# MM32F3277_Balance.net
KiCad netlist of a schematic drawn in Altium Designer
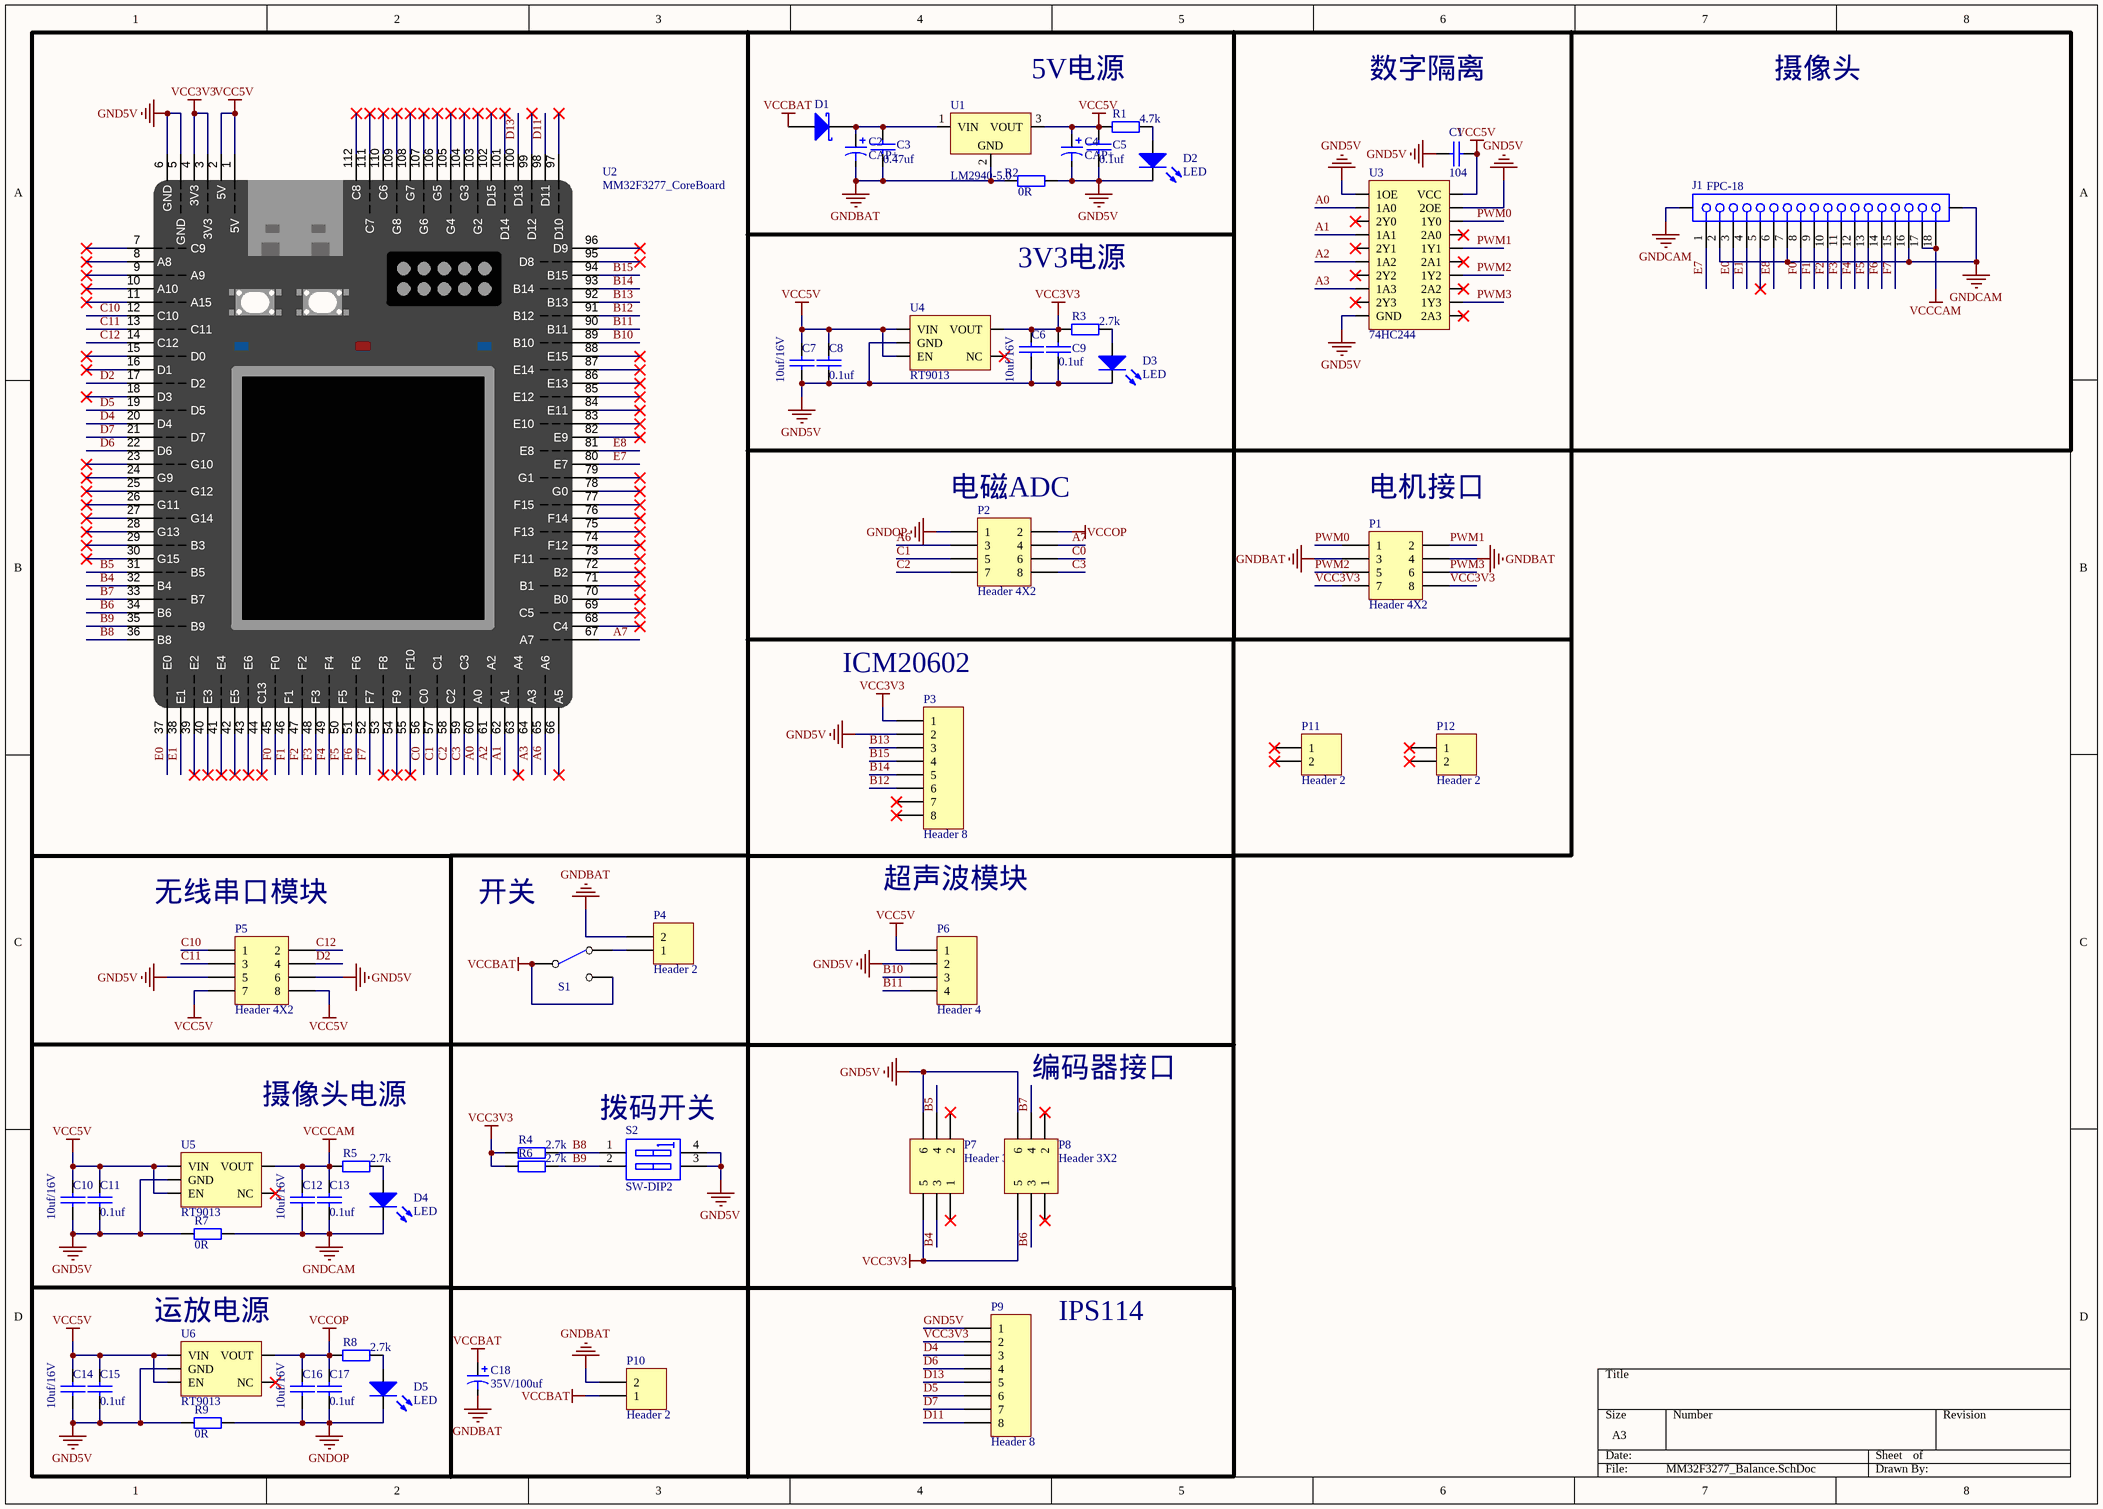
[diagram p0: MM32F3277_Balance.SchDoc]

(export (version "E")
  (design (tool "Eeschema 10.0.6"))
  (components
    (comp (ref "C1")
      (value "104")
      (footprint "0603C")
      (description "Capacitor")
      (libsource (lib "ywh") (part "CAP"))
    )
    (comp (ref "C2")
      (value "CAP+")
      (footprint "CS 2.5*6.3*11 - V")
      (description "Capacitor")
      (libsource (lib "ywh") (part "CAP+"))
    )
    (comp (ref "C3")
      (value "0.47uf")
      (footprint "0603C")
      (description "Capacitor")
      (libsource (lib "ywh") (part "CAP"))
    )
    (comp (ref "C4")
      (value "CAP+")
      (footprint "CS 2.5*6.3*7 - R")
      (description "Capacitor")
      (libsource (lib "ywh") (part "CAP+"))
    )
    (comp (ref "C5")
      (value "0.1uf")
      (footprint "0603C")
      (description "Capacitor")
      (libsource (lib "ywh") (part "CAP"))
    )
    (comp (ref "C6")
      (value "10uf/16V")
      (footprint "1206C")
      (description "Capacitor")
      (libsource (lib "ywh") (part "CAP"))
    )
    (comp (ref "C7")
      (value "10uf/16V")
      (footprint "1206C")
      (description "Capacitor")
      (libsource (lib "ywh") (part "CAP"))
    )
    (comp (ref "C8")
      (value "0.1uf")
      (footprint "0603C")
      (description "Capacitor")
      (libsource (lib "ywh") (part "CAP"))
    )
    (comp (ref "C9")
      (value "0.1uf")
      (footprint "0603C")
      (description "Capacitor")
      (libsource (lib "ywh") (part "CAP"))
    )
    (comp (ref "C10")
      (value "10uf/16V")
      (footprint "1206C")
      (description "Capacitor")
      (libsource (lib "ywh") (part "CAP"))
    )
    (comp (ref "C11")
      (value "0.1uf")
      (footprint "0603C")
      (description "Capacitor")
      (libsource (lib "ywh") (part "CAP"))
    )
    (comp (ref "C12")
      (value "10uf/16V")
      (footprint "1206C")
      (description "Capacitor")
      (libsource (lib "ywh") (part "CAP"))
    )
    (comp (ref "C13")
      (value "0.1uf")
      (footprint "0603C")
      (description "Capacitor")
      (libsource (lib "ywh") (part "CAP"))
    )
    (comp (ref "C14")
      (value "10uf/16V")
      (footprint "1206C")
      (description "Capacitor")
      (libsource (lib "ywh") (part "CAP"))
    )
    (comp (ref "C15")
      (value "0.1uf")
      (footprint "0603C")
      (description "Capacitor")
      (libsource (lib "ywh") (part "CAP"))
    )
    (comp (ref "C16")
      (value "10uf/16V")
      (footprint "1206C")
      (description "Capacitor")
      (libsource (lib "ywh") (part "CAP"))
    )
    (comp (ref "C17")
      (value "0.1uf")
      (footprint "0603C")
      (description "Capacitor")
      (libsource (lib "ywh") (part "CAP"))
    )
    (comp (ref "C18")
      (value "35V/100uf")
      (footprint "CS 2.5*6.3*7 - R")
      (description "Capacitor")
      (libsource (lib "ywh") (part "CAP+"))
    )
    (comp (ref "D1")
      (value "DIODE3")
      (footprint "SMA - duplicate")
      (fields (field (name "PUBLISHER") "Altium Limited"))
      (libsource (lib "ywh") (part "DIODE3"))
    )
    (comp (ref "D2")
      (value "LED")
      (footprint "LED 0603W")
      (description "Led")
      (libsource (lib "ywh") (part "LED"))
    )
    (comp (ref "D3")
      (value "LED")
      (footprint "LED 0603W")
      (description "Led")
      (libsource (lib "ywh") (part "LED"))
    )
    (comp (ref "D4")
      (value "LED")
      (footprint "LED 0603W")
      (description "Led")
      (libsource (lib "ywh") (part "LED"))
    )
    (comp (ref "D5")
      (value "LED")
      (footprint "LED 0603W")
      (description "Led")
      (libsource (lib "ywh") (part "LED"))
    )
    (comp (ref "J1") (value "FPC-18") (footprint "FPC0.5 2H-WS-18P") (libsource (lib "ywh") (part "FPC-18")))
    (comp (ref "P1")
      (value "Header 4X2")
      (footprint "HDR2X4")
      (description "Header, 4-Pin, Dual row")
      (fields (field (name "PUBLISHER") "Altium Limited"))
      (libsource (lib "ywh") (part "Header 4X2"))
    )
    (comp (ref "P2")
      (value "Header 4X2")
      (footprint "HDR2X4")
      (description "Header, 4-Pin, Dual row")
      (fields (field (name "PUBLISHER") "Altium Limited"))
      (libsource (lib "ywh") (part "Header 4X2"))
    )
    (comp (ref "P3")
      (value "Header 8")
      (footprint "XH2.54-LI-8P")
      (description "Header, 8-Pin")
      (fields (field (name "PUBLISHER") "Altium Limited"))
      (libsource (lib "ywh") (part "Header 8"))
    )
    (comp (ref "P4")
      (value "Header 2")
      (footprint "T型头")
      (description "Header, 2-Pin")
      (fields (field (name "PUBLISHER") "Altium Limited"))
      (libsource (lib "") (part "Header 2_1"))
    )
    (comp (ref "P5")
      (value "Header 4X2")
      (footprint "HDR2X4")
      (description "Header, 4-Pin, Dual row")
      (fields (field (name "PUBLISHER") "Altium Limited"))
      (libsource (lib "ywh") (part "Header 4X2"))
    )
    (comp (ref "P6")
      (value "Header 4")
      (footprint "HDR1X4")
      (description "Header, 4-Pin")
      (fields (field (name "PUBLISHER") "Altium Limited"))
      (libsource (lib "ywh") (part "Header 4"))
    )
    (comp (ref "P7")
      (value "Header 3X2")
      (footprint "HDR2X3")
      (description "Header, 3-Pin, Dual row")
      (fields (field (name "PUBLISHER") "Altium Limited"))
      (libsource (lib "ywh") (part "Header 3X2"))
    )
    (comp (ref "P8")
      (value "Header 3X2")
      (footprint "HDR2X3")
      (description "Header, 3-Pin, Dual row")
      (fields (field (name "PUBLISHER") "Altium Limited"))
      (libsource (lib "ywh") (part "Header 3X2"))
    )
    (comp (ref "P9")
      (value "Header 8")
      (footprint "HDR1X8")
      (description "Header, 8-Pin")
      (fields (field (name "PUBLISHER") "Altium Limited"))
      (libsource (lib "ywh") (part "Header 8"))
    )
    (comp (ref "P10")
      (value "Header 2")
      (footprint "电源焊孔")
      (description "Header, 2-Pin")
      (fields (field (name "PUBLISHER") "Altium Limited"))
      (libsource (lib "") (part "Header 2_1"))
    )
    (comp (ref "P11")
      (value "Header 2")
      (footprint "HDR1X2")
      (description "Header, 2-Pin")
      (fields (field (name "PUBLISHER") "Altium Limited"))
      (libsource (lib "ywh") (part "Header 2"))
    )
    (comp (ref "P12")
      (value "Header 2")
      (footprint "HDR1X2")
      (description "Header, 2-Pin")
      (fields (field (name "PUBLISHER") "Altium Limited"))
      (libsource (lib "ywh") (part "Header 2"))
    )
    (comp (ref "R1")
      (value "4.7k")
      (footprint "0603R")
      (description "Resistor")
      (libsource (lib "ywh") (part "Res"))
    )
    (comp (ref "R2")
      (value "0R")
      (footprint "0603R")
      (description "Resistor")
      (libsource (lib "ywh") (part "Res"))
    )
    (comp (ref "R3")
      (value "2.7k")
      (footprint "0603R")
      (description "Resistor")
      (libsource (lib "ywh") (part "Res"))
    )
    (comp (ref "R4")
      (value "2.7k")
      (footprint "0603R")
      (description "Resistor")
      (libsource (lib "ywh") (part "Res"))
    )
    (comp (ref "R5")
      (value "2.7k")
      (footprint "0603R")
      (description "Resistor")
      (libsource (lib "ywh") (part "Res"))
    )
    (comp (ref "R6")
      (value "2.7k")
      (footprint "0603R")
      (description "Resistor")
      (libsource (lib "ywh") (part "Res"))
    )
    (comp (ref "R7")
      (value "0R")
      (footprint "0603R")
      (description "Resistor")
      (libsource (lib "ywh") (part "Res"))
    )
    (comp (ref "R8")
      (value "2.7k")
      (footprint "0603R")
      (description "Resistor")
      (libsource (lib "ywh") (part "Res"))
    )
    (comp (ref "R9")
      (value "0R")
      (footprint "0603R")
      (description "Resistor")
      (libsource (lib "ywh") (part "Res"))
    )
    (comp (ref "S1") (value "双刀单柄开关") (footprint "MTS-10x") (libsource (lib "ywh") (part "双刀单柄开关")))
    (comp (ref "S2")
      (value "SW-DIP2")
      (footprint "CSW DIP-2P_G")
      (description "DIP Switch")
      (libsource (lib "ywh") (part "SW-DIP2"))
    )
    (comp (ref "U1") (value "LM2940-5.0") (footprint "SOT-223") (libsource (lib "ywh") (part "LM2940-5.0")))
    (comp (ref "U2")
      (value "MM32F3277_CoreBoard")
      (footprint "MM32F3277_CoreBoard")
      (description "逐飞科技MM32F3277核心板")
      (libsource (lib "MM32F3277核心板整体原理") (part "MM32F3277_CoreBoard"))
    )
    (comp (ref "U3") (value "74HC244") (footprint "TSSOP20") (libsource (lib "ywh") (part "74HC244")))
    (comp (ref "U4") (value "RT9013") (footprint "SOT23-5") (libsource (lib "ywh") (part "RT9013")))
    (comp (ref "U5") (value "RT9013") (footprint "SOT23-5") (libsource (lib "ywh") (part "RT9013")))
    (comp (ref "U6") (value "RT9013") (footprint "SOT23-5") (libsource (lib "ywh") (part "RT9013")))
  )
  (nets
    (net (code "1") (name "/A0") (class "Default")
      (node (ref "U2") (pin "60") (pinfunction "A0_60") (pintype "passive"))
      (node (ref "U3") (pin "2") (pinfunction "1A0_2") (pintype "passive"))
    )
    (net (code "2") (name "/A1") (class "Default")
      (node (ref "U2") (pin "62") (pinfunction "A1_62") (pintype "passive"))
      (node (ref "U3") (pin "4") (pinfunction "1A1_4") (pintype "passive"))
    )
    (net (code "3") (name "/A2") (class "Default")
      (node (ref "U2") (pin "61") (pinfunction "A2_61") (pintype "passive"))
      (node (ref "U3") (pin "6") (pinfunction "1A2_6") (pintype "passive"))
    )
    (net (code "4") (name "/A3") (class "Default")
      (node (ref "U2") (pin "64") (pinfunction "A3_64") (pintype "passive"))
      (node (ref "U3") (pin "8") (pinfunction "1A3_8") (pintype "passive"))
    )
    (net (code "5") (name "/A6") (class "Default")
      (node (ref "P2") (pin "3") (pinfunction "3_3") (pintype "passive"))
      (node (ref "U2") (pin "65") (pinfunction "A6_65") (pintype "passive"))
    )
    (net (code "6") (name "/A7") (class "Default")
      (node (ref "P2") (pin "4") (pinfunction "4_4") (pintype "passive"))
      (node (ref "U2") (pin "67") (pinfunction "A7_67") (pintype "passive"))
    )
    (net (code "7") (name "/B4") (class "Default")
      (node (ref "P7") (pin "3") (pinfunction "3_3") (pintype "passive"))
      (node (ref "U2") (pin "32") (pinfunction "B4_32") (pintype "passive"))
    )
    (net (code "8") (name "/B5") (class "Default")
      (node (ref "P7") (pin "4") (pinfunction "4_4") (pintype "passive"))
      (node (ref "U2") (pin "31") (pinfunction "B5_31") (pintype "passive"))
    )
    (net (code "9") (name "/B6") (class "Default")
      (node (ref "P8") (pin "3") (pinfunction "3_3") (pintype "passive"))
      (node (ref "U2") (pin "34") (pinfunction "B6_34") (pintype "passive"))
    )
    (net (code "10") (name "/B7") (class "Default")
      (node (ref "P8") (pin "4") (pinfunction "4_4") (pintype "passive"))
      (node (ref "U2") (pin "33") (pinfunction "B7_33") (pintype "passive"))
    )
    (net (code "11") (name "/B8") (class "Default")
      (node (ref "R4") (pin "2") (pinfunction "2_2") (pintype "passive"))
      (node (ref "S2") (pin "1") (pinfunction "A1_1") (pintype "passive"))
      (node (ref "U2") (pin "36") (pinfunction "B8_36") (pintype "passive"))
    )
    (net (code "12") (name "/B9") (class "Default")
      (node (ref "R6") (pin "2") (pinfunction "2_2") (pintype "passive"))
      (node (ref "S2") (pin "2") (pinfunction "A2_2") (pintype "passive"))
      (node (ref "U2") (pin "35") (pinfunction "B9_35") (pintype "passive"))
    )
    (net (code "13") (name "/B10") (class "Default")
      (node (ref "P6") (pin "3") (pinfunction "3_3") (pintype "passive"))
      (node (ref "U2") (pin "89") (pinfunction "B10_89") (pintype "passive"))
    )
    (net (code "14") (name "/B11") (class "Default")
      (node (ref "P6") (pin "4") (pinfunction "4_4") (pintype "passive"))
      (node (ref "U2") (pin "90") (pinfunction "B11_90") (pintype "passive"))
    )
    (net (code "15") (name "/B12") (class "Default")
      (node (ref "P3") (pin "6") (pinfunction "6_6") (pintype "passive"))
      (node (ref "U2") (pin "91") (pinfunction "B12_91") (pintype "passive"))
    )
    (net (code "16") (name "/B13") (class "Default")
      (node (ref "P3") (pin "3") (pinfunction "3_3") (pintype "passive"))
      (node (ref "U2") (pin "92") (pinfunction "B13_92") (pintype "passive"))
    )
    (net (code "17") (name "/B14") (class "Default")
      (node (ref "P3") (pin "5") (pinfunction "5_5") (pintype "passive"))
      (node (ref "U2") (pin "93") (pinfunction "B14_93") (pintype "passive"))
    )
    (net (code "18") (name "/B15") (class "Default")
      (node (ref "P3") (pin "4") (pinfunction "4_4") (pintype "passive"))
      (node (ref "U2") (pin "94") (pinfunction "B15_94") (pintype "passive"))
    )
    (net (code "19") (name "/C0") (class "Default")
      (node (ref "P2") (pin "6") (pinfunction "6_6") (pintype "passive"))
      (node (ref "U2") (pin "56") (pinfunction "C0_56") (pintype "passive"))
    )
    (net (code "20") (name "/C1") (class "Default")
      (node (ref "P2") (pin "5") (pinfunction "5_5") (pintype "passive"))
      (node (ref "U2") (pin "57") (pinfunction "C1_57") (pintype "passive"))
    )
    (net (code "21") (name "/C2") (class "Default")
      (node (ref "P2") (pin "7") (pinfunction "7_7") (pintype "passive"))
      (node (ref "U2") (pin "58") (pinfunction "C2_58") (pintype "passive"))
    )
    (net (code "22") (name "/C3") (class "Default")
      (node (ref "P2") (pin "8") (pinfunction "8_8") (pintype "passive"))
      (node (ref "U2") (pin "59") (pinfunction "C3_59") (pintype "passive"))
    )
    (net (code "23") (name "/C10") (class "Default")
      (node (ref "P5") (pin "1") (pinfunction "1_1") (pintype "passive"))
      (node (ref "U2") (pin "12") (pinfunction "C10_12") (pintype "passive"))
    )
    (net (code "24") (name "/C11") (class "Default")
      (node (ref "P5") (pin "3") (pinfunction "3_3") (pintype "passive"))
      (node (ref "U2") (pin "13") (pinfunction "C11_13") (pintype "passive"))
    )
    (net (code "25") (name "/C12") (class "Default")
      (node (ref "P5") (pin "2") (pinfunction "2_2") (pintype "passive"))
      (node (ref "U2") (pin "14") (pinfunction "C12_14") (pintype "passive"))
    )
    (net (code "26") (name "/D2") (class "Default")
      (node (ref "P5") (pin "4") (pinfunction "4_4") (pintype "passive"))
      (node (ref "U2") (pin "17") (pinfunction "D2_17") (pintype "passive"))
    )
    (net (code "27") (name "/D4") (class "Default")
      (node (ref "P9") (pin "3") (pinfunction "3_3") (pintype "passive"))
      (node (ref "U2") (pin "20") (pinfunction "D4_20") (pintype "passive"))
    )
    (net (code "28") (name "/D5") (class "Default")
      (node (ref "P9") (pin "6") (pinfunction "6_6") (pintype "passive"))
      (node (ref "U2") (pin "19") (pinfunction "D5_19") (pintype "passive"))
    )
    (net (code "29") (name "/D6") (class "Default")
      (node (ref "P9") (pin "4") (pinfunction "4_4") (pintype "passive"))
      (node (ref "U2") (pin "22") (pinfunction "D6_22") (pintype "passive"))
    )
    (net (code "30") (name "/D7") (class "Default")
      (node (ref "P9") (pin "7") (pinfunction "7_7") (pintype "passive"))
      (node (ref "U2") (pin "21") (pinfunction "D7_21") (pintype "passive"))
    )
    (net (code "31") (name "/D11") (class "Default")
      (node (ref "P9") (pin "8") (pinfunction "8_8") (pintype "passive"))
      (node (ref "U2") (pin "98") (pinfunction "D11_98") (pintype "passive"))
    )
    (net (code "32") (name "/D13") (class "Default")
      (node (ref "P9") (pin "5") (pinfunction "5_5") (pintype "passive"))
      (node (ref "U2") (pin "100") (pinfunction "D13_100") (pintype "passive"))
    )
    (net (code "33") (name "/E0") (class "Default")
      (node (ref "J1") (pin "3") (pinfunction "3_3") (pintype "passive"))
      (node (ref "U2") (pin "37") (pinfunction "E0_37") (pintype "passive"))
    )
    (net (code "34") (name "/E1") (class "Default")
      (node (ref "J1") (pin "4") (pinfunction "4_4") (pintype "passive"))
      (node (ref "U2") (pin "38") (pinfunction "E1_38") (pintype "passive"))
    )
    (net (code "35") (name "/E7") (class "Default")
      (node (ref "J1") (pin "1") (pinfunction "1_1") (pintype "passive"))
      (node (ref "U2") (pin "80") (pinfunction "E7_80") (pintype "passive"))
    )
    (net (code "36") (name "/E8") (class "Default")
      (node (ref "J1") (pin "6") (pinfunction "6_6") (pintype "passive"))
      (node (ref "U2") (pin "81") (pinfunction "E8_81") (pintype "passive"))
    )
    (net (code "37") (name "/F0") (class "Default")
      (node (ref "J1") (pin "8") (pinfunction "8_8") (pintype "passive"))
      (node (ref "U2") (pin "45") (pinfunction "F0_45") (pintype "passive"))
    )
    (net (code "38") (name "/F1") (class "Default")
      (node (ref "J1") (pin "9") (pinfunction "9_9") (pintype "passive"))
      (node (ref "U2") (pin "46") (pinfunction "F1_46") (pintype "passive"))
    )
    (net (code "39") (name "/F2") (class "Default")
      (node (ref "J1") (pin "10") (pinfunction "10_10") (pintype "passive"))
      (node (ref "U2") (pin "47") (pinfunction "F2_47") (pintype "passive"))
    )
    (net (code "40") (name "/F3") (class "Default")
      (node (ref "J1") (pin "11") (pinfunction "11_11") (pintype "passive"))
      (node (ref "U2") (pin "48") (pinfunction "F3_48") (pintype "passive"))
    )
    (net (code "41") (name "/F4") (class "Default")
      (node (ref "J1") (pin "12") (pinfunction "12_12") (pintype "passive"))
      (node (ref "U2") (pin "49") (pinfunction "F4_49") (pintype "passive"))
    )
    (net (code "42") (name "/F5") (class "Default")
      (node (ref "J1") (pin "13") (pinfunction "13_13") (pintype "passive"))
      (node (ref "U2") (pin "50") (pinfunction "F5_50") (pintype "passive"))
    )
    (net (code "43") (name "/F6") (class "Default")
      (node (ref "J1") (pin "14") (pinfunction "14_14") (pintype "passive"))
      (node (ref "U2") (pin "51") (pinfunction "F6_51") (pintype "passive"))
    )
    (net (code "44") (name "/F7") (class "Default")
      (node (ref "J1") (pin "15") (pinfunction "15_15") (pintype "passive"))
      (node (ref "U2") (pin "52") (pinfunction "F7_52") (pintype "passive"))
    )
    (net (code "45") (name "/PWM0") (class "Default")
      (node (ref "P1") (pin "1") (pinfunction "1_1") (pintype "passive"))
      (node (ref "U3") (pin "18") (pinfunction "1Y0_18") (pintype "passive"))
    )
    (net (code "46") (name "/PWM1") (class "Default")
      (node (ref "P1") (pin "2") (pinfunction "2_2") (pintype "passive"))
      (node (ref "U3") (pin "16") (pinfunction "1Y1_16") (pintype "passive"))
    )
    (net (code "47") (name "/PWM2") (class "Default")
      (node (ref "P1") (pin "5") (pinfunction "5_5") (pintype "passive"))
      (node (ref "U3") (pin "14") (pinfunction "1Y2_14") (pintype "passive"))
    )
    (net (code "48") (name "/PWM3") (class "Default")
      (node (ref "P1") (pin "6") (pinfunction "6_6") (pintype "passive"))
      (node (ref "U3") (pin "12") (pinfunction "1Y3_12") (pintype "passive"))
    )
    (net (code "49") (name "GND5V") (class "Default")
      (node (ref "C1") (pin "1") (pinfunction "1_1") (pintype "passive"))
      (node (ref "C10") (pin "1") (pinfunction "1_1") (pintype "passive"))
      (node (ref "C11") (pin "1") (pinfunction "1_1") (pintype "passive"))
      (node (ref "C14") (pin "1") (pinfunction "1_1") (pintype "passive"))
      (node (ref "C15") (pin "1") (pinfunction "1_1") (pintype "passive"))
      (node (ref "C4") (pin "2") (pinfunction "2_2") (pintype "passive"))
      (node (ref "C5") (pin "1") (pinfunction "1_1") (pintype "passive"))
      (node (ref "C6") (pin "1") (pinfunction "1_1") (pintype "passive"))
      (node (ref "C7") (pin "1") (pinfunction "1_1") (pintype "passive"))
      (node (ref "C8") (pin "1") (pinfunction "1_1") (pintype "passive"))
      (node (ref "C9") (pin "1") (pinfunction "1_1") (pintype "passive"))
      (node (ref "D2") (pin "2") (pinfunction "K_2") (pintype "passive"))
      (node (ref "D3") (pin "2") (pinfunction "K_2") (pintype "passive"))
      (node (ref "P3") (pin "2") (pinfunction "2_2") (pintype "passive"))
      (node (ref "P5") (pin "5") (pinfunction "5_5") (pintype "passive"))
      (node (ref "P5") (pin "6") (pinfunction "6_6") (pintype "passive"))
      (node (ref "P6") (pin "2") (pinfunction "2_2") (pintype "passive"))
      (node (ref "P7") (pin "6") (pinfunction "6_6") (pintype "passive"))
      (node (ref "P8") (pin "6") (pinfunction "6_6") (pintype "passive"))
      (node (ref "P9") (pin "1") (pinfunction "1_1") (pintype "passive"))
      (node (ref "R2") (pin "2") (pinfunction "2_2") (pintype "passive"))
      (node (ref "R7") (pin "1") (pinfunction "1_1") (pintype "passive"))
      (node (ref "R9") (pin "1") (pinfunction "1_1") (pintype "passive"))
      (node (ref "S2") (pin "3") (pinfunction "B2_3") (pintype "passive"))
      (node (ref "S2") (pin "4") (pinfunction "B1_4") (pintype "passive"))
      (node (ref "U2") (pin "5") (pinfunction "GND_5") (pintype "passive"))
      (node (ref "U2") (pin "6") (pinfunction "GND_6") (pintype "passive"))
      (node (ref "U3") (pin "1") (pinfunction "1OE_1") (pintype "passive"))
      (node (ref "U3") (pin "10") (pinfunction "GND_10") (pintype "passive"))
      (node (ref "U3") (pin "19") (pinfunction "2OE_19") (pintype "passive"))
      (node (ref "U4") (pin "2") (pinfunction "GND_2") (pintype "passive"))
      (node (ref "U5") (pin "2") (pinfunction "GND_2") (pintype "passive"))
      (node (ref "U6") (pin "2") (pinfunction "GND_2") (pintype "passive"))
    )
    (net (code "50") (name "GNDBAT") (class "Default")
      (node (ref "C18") (pin "2") (pinfunction "2_2") (pintype "passive"))
      (node (ref "C2") (pin "2") (pinfunction "2_2") (pintype "passive"))
      (node (ref "C3") (pin "1") (pinfunction "1_1") (pintype "passive"))
      (node (ref "P1") (pin "3") (pinfunction "3_3") (pintype "passive"))
      (node (ref "P1") (pin "4") (pinfunction "4_4") (pintype "passive"))
      (node (ref "P10") (pin "2") (pinfunction "2_2") (pintype "passive"))
      (node (ref "P4") (pin "2") (pinfunction "2_2") (pintype "passive"))
      (node (ref "R2") (pin "1") (pinfunction "1_1") (pintype "passive"))
      (node (ref "U1") (pin "2") (pinfunction "GND_2") (pintype "passive"))
    )
    (net (code "51") (name "GNDCAM") (class "Default")
      (node (ref "C12") (pin "1") (pinfunction "1_1") (pintype "passive"))
      (node (ref "C13") (pin "1") (pinfunction "1_1") (pintype "passive"))
      (node (ref "D4") (pin "2") (pinfunction "K_2") (pintype "passive"))
      (node (ref "J1") (pin "0") (pinfunction "0_0") (pintype "passive"))
      (node (ref "J1") (pin "16") (pinfunction "16_16") (pintype "passive"))
      (node (ref "J1") (pin "2") (pinfunction "2_2") (pintype "passive"))
      (node (ref "J1") (pin "7") (pinfunction "7_7") (pintype "passive"))
      (node (ref "R7") (pin "2") (pinfunction "2_2") (pintype "passive"))
    )
    (net (code "52") (name "GNDOP") (class "Default")
      (node (ref "C16") (pin "1") (pinfunction "1_1") (pintype "passive"))
      (node (ref "C17") (pin "1") (pinfunction "1_1") (pintype "passive"))
      (node (ref "D5") (pin "2") (pinfunction "K_2") (pintype "passive"))
      (node (ref "P2") (pin "1") (pinfunction "1_1") (pintype "passive"))
      (node (ref "R9") (pin "2") (pinfunction "2_2") (pintype "passive"))
    )
    (net (code "53") (name "Net-(D1-K)") (class "Default")
      (node (ref "C2") (pin "1") (pinfunction "1_1") (pintype "passive"))
      (node (ref "C3") (pin "2") (pinfunction "2_2") (pintype "passive"))
      (node (ref "D1") (pin "2") (pinfunction "K_2") (pintype "passive"))
      (node (ref "U1") (pin "1") (pinfunction "VIN_1") (pintype "passive"))
    )
    (net (code "54") (name "Net-(D2-A)") (class "Default")
      (node (ref "D2") (pin "1") (pinfunction "A_1") (pintype "passive"))
      (node (ref "R1") (pin "2") (pinfunction "2_2") (pintype "passive"))
    )
    (net (code "55") (name "Net-(D3-A)") (class "Default")
      (node (ref "D3") (pin "1") (pinfunction "A_1") (pintype "passive"))
      (node (ref "R3") (pin "2") (pinfunction "2_2") (pintype "passive"))
    )
    (net (code "56") (name "Net-(D4-A)") (class "Default")
      (node (ref "D4") (pin "1") (pinfunction "A_1") (pintype "passive"))
      (node (ref "R5") (pin "2") (pinfunction "2_2") (pintype "passive"))
    )
    (net (code "57") (name "Net-(D5-A)") (class "Default")
      (node (ref "D5") (pin "1") (pinfunction "A_1") (pintype "passive"))
      (node (ref "R8") (pin "2") (pinfunction "2_2") (pintype "passive"))
    )
    (net (code "58") (name "Net-(S1-NC)") (class "Default")
      (node (ref "P4") (pin "1") (pinfunction "1_1") (pintype "passive"))
      (node (ref "S1") (pin "1") (pinfunction "NC_1") (pintype "passive"))
    )
    (net (code "59") (name "VCC3V3") (class "Default")
      (node (ref "C6") (pin "2") (pinfunction "2_2") (pintype "passive"))
      (node (ref "C9") (pin "2") (pinfunction "2_2") (pintype "passive"))
      (node (ref "P1") (pin "7") (pinfunction "7_7") (pintype "passive"))
      (node (ref "P1") (pin "8") (pinfunction "8_8") (pintype "passive"))
      (node (ref "P3") (pin "1") (pinfunction "1_1") (pintype "passive"))
      (node (ref "P7") (pin "5") (pinfunction "5_5") (pintype "passive"))
      (node (ref "P8") (pin "5") (pinfunction "5_5") (pintype "passive"))
      (node (ref "P9") (pin "2") (pinfunction "2_2") (pintype "passive"))
      (node (ref "R3") (pin "1") (pinfunction "1_1") (pintype "passive"))
      (node (ref "R4") (pin "1") (pinfunction "1_1") (pintype "passive"))
      (node (ref "R6") (pin "1") (pinfunction "1_1") (pintype "passive"))
      (node (ref "U2") (pin "3") (pinfunction "3V3_3") (pintype "passive"))
      (node (ref "U2") (pin "4") (pinfunction "3V3_4") (pintype "passive"))
      (node (ref "U4") (pin "5") (pinfunction "VOUT_5") (pintype "passive"))
    )
    (net (code "60") (name "VCC5V") (class "Default")
      (node (ref "C1") (pin "2") (pinfunction "2_2") (pintype "passive"))
      (node (ref "C10") (pin "2") (pinfunction "2_2") (pintype "passive"))
      (node (ref "C11") (pin "2") (pinfunction "2_2") (pintype "passive"))
      (node (ref "C14") (pin "2") (pinfunction "2_2") (pintype "passive"))
      (node (ref "C15") (pin "2") (pinfunction "2_2") (pintype "passive"))
      (node (ref "C4") (pin "1") (pinfunction "1_1") (pintype "passive"))
      (node (ref "C5") (pin "2") (pinfunction "2_2") (pintype "passive"))
      (node (ref "C7") (pin "2") (pinfunction "2_2") (pintype "passive"))
      (node (ref "C8") (pin "2") (pinfunction "2_2") (pintype "passive"))
      (node (ref "P5") (pin "7") (pinfunction "7_7") (pintype "passive"))
      (node (ref "P5") (pin "8") (pinfunction "8_8") (pintype "passive"))
      (node (ref "P6") (pin "1") (pinfunction "1_1") (pintype "passive"))
      (node (ref "R1") (pin "1") (pinfunction "1_1") (pintype "passive"))
      (node (ref "U1") (pin "3") (pinfunction "VOUT_3") (pintype "passive"))
      (node (ref "U2") (pin "1") (pinfunction "5V_1") (pintype "passive"))
      (node (ref "U2") (pin "2") (pinfunction "5V_2") (pintype "passive"))
      (node (ref "U3") (pin "20") (pinfunction "VCC_20") (pintype "passive"))
      (node (ref "U4") (pin "1") (pinfunction "VIN_1") (pintype "passive"))
      (node (ref "U4") (pin "3") (pinfunction "EN_3") (pintype "passive"))
      (node (ref "U5") (pin "1") (pinfunction "VIN_1") (pintype "passive"))
      (node (ref "U5") (pin "3") (pinfunction "EN_3") (pintype "passive"))
      (node (ref "U6") (pin "1") (pinfunction "VIN_1") (pintype "passive"))
      (node (ref "U6") (pin "3") (pinfunction "EN_3") (pintype "passive"))
    )
    (net (code "61") (name "VCCBAT") (class "Default")
      (node (ref "C18") (pin "1") (pinfunction "1_1") (pintype "passive"))
      (node (ref "D1") (pin "1") (pinfunction "A_1") (pintype "passive"))
      (node (ref "P10") (pin "1") (pinfunction "1_1") (pintype "passive"))
      (node (ref "S1") (pin "2") (pinfunction "COMMON_2") (pintype "passive"))
      (node (ref "S1") (pin "3") (pinfunction "NO_3") (pintype "passive"))
    )
    (net (code "62") (name "VCCCAM") (class "Default")
      (node (ref "C12") (pin "2") (pinfunction "2_2") (pintype "passive"))
      (node (ref "C13") (pin "2") (pinfunction "2_2") (pintype "passive"))
      (node (ref "J1") (pin "17") (pinfunction "17_17") (pintype "passive"))
      (node (ref "J1") (pin "18") (pinfunction "18_18") (pintype "passive"))
      (node (ref "R5") (pin "1") (pinfunction "1_1") (pintype "passive"))
      (node (ref "U5") (pin "5") (pinfunction "VOUT_5") (pintype "passive"))
    )
    (net (code "63") (name "VCCOP") (class "Default")
      (node (ref "C16") (pin "2") (pinfunction "2_2") (pintype "passive"))
      (node (ref "C17") (pin "2") (pinfunction "2_2") (pintype "passive"))
      (node (ref "P2") (pin "2") (pinfunction "2_2") (pintype "passive"))
      (node (ref "R8") (pin "1") (pinfunction "1_1") (pintype "passive"))
      (node (ref "U6") (pin "5") (pinfunction "VOUT_5") (pintype "passive"))
    )
    (net (code "64") (name "unconnected-(J1-Pad5)") (class "Default")
      (node (ref "J1") (pin "5") (pinfunction "5_5") (pintype "passive+no_connect"))
    )
    (net (code "65") (name "unconnected-(P3-Pad7)") (class "Default")
      (node (ref "P3") (pin "7") (pinfunction "7_7") (pintype "passive+no_connect"))
    )
    (net (code "66") (name "unconnected-(P3-Pad8)") (class "Default")
      (node (ref "P3") (pin "8") (pinfunction "8_8") (pintype "passive+no_connect"))
    )
    (net (code "67") (name "unconnected-(P7-Pad1)") (class "Default")
      (node (ref "P7") (pin "1") (pinfunction "1_1") (pintype "passive+no_connect"))
    )
    (net (code "68") (name "unconnected-(P7-Pad2)") (class "Default")
      (node (ref "P7") (pin "2") (pinfunction "2_2") (pintype "passive+no_connect"))
    )
    (net (code "69") (name "unconnected-(P8-Pad1)") (class "Default")
      (node (ref "P8") (pin "1") (pinfunction "1_1") (pintype "passive+no_connect"))
    )
    (net (code "70") (name "unconnected-(P8-Pad2)") (class "Default")
      (node (ref "P8") (pin "2") (pinfunction "2_2") (pintype "passive+no_connect"))
    )
    (net (code "71") (name "unconnected-(P11-Pad1)") (class "Default")
      (node (ref "P11") (pin "1") (pinfunction "1_1") (pintype "passive+no_connect"))
    )
    (net (code "72") (name "unconnected-(P11-Pad2)") (class "Default")
      (node (ref "P11") (pin "2") (pinfunction "2_2") (pintype "passive+no_connect"))
    )
    (net (code "73") (name "unconnected-(P12-Pad1)") (class "Default")
      (node (ref "P12") (pin "1") (pinfunction "1_1") (pintype "passive+no_connect"))
    )
    (net (code "74") (name "unconnected-(P12-Pad2)") (class "Default")
      (node (ref "P12") (pin "2") (pinfunction "2_2") (pintype "passive+no_connect"))
    )
    (net (code "75") (name "unconnected-(U2-A4-Pad63)") (class "Default")
      (node (ref "U2") (pin "63") (pinfunction "A4_63") (pintype "passive+no_connect"))
    )
    (net (code "76") (name "unconnected-(U2-A5-Pad66)") (class "Default")
      (node (ref "U2") (pin "66") (pinfunction "A5_66") (pintype "passive+no_connect"))
    )
    (net (code "77") (name "unconnected-(U2-A8-Pad8)") (class "Default")
      (node (ref "U2") (pin "8") (pinfunction "A8_8") (pintype "passive+no_connect"))
    )
    (net (code "78") (name "unconnected-(U2-A9-Pad9)") (class "Default")
      (node (ref "U2") (pin "9") (pinfunction "A9_9") (pintype "passive+no_connect"))
    )
    (net (code "79") (name "unconnected-(U2-A10-Pad10)") (class "Default")
      (node (ref "U2") (pin "10") (pinfunction "A10_10") (pintype "passive+no_connect"))
    )
    (net (code "80") (name "unconnected-(U2-A15-Pad11)") (class "Default")
      (node (ref "U2") (pin "11") (pinfunction "A15_11") (pintype "passive+no_connect"))
    )
    (net (code "81") (name "unconnected-(U2-B0-Pad70)") (class "Default")
      (node (ref "U2") (pin "70") (pinfunction "B0_70") (pintype "passive+no_connect"))
    )
    (net (code "82") (name "unconnected-(U2-B1-Pad71)") (class "Default")
      (node (ref "U2") (pin "71") (pinfunction "B1_71") (pintype "passive+no_connect"))
    )
    (net (code "83") (name "unconnected-(U2-B2-Pad72)") (class "Default")
      (node (ref "U2") (pin "72") (pinfunction "B2_72") (pintype "passive+no_connect"))
    )
    (net (code "84") (name "unconnected-(U2-B3-Pad29)") (class "Default")
      (node (ref "U2") (pin "29") (pinfunction "B3_29") (pintype "passive+no_connect"))
    )
    (net (code "85") (name "unconnected-(U2-C4-Pad68)") (class "Default")
      (node (ref "U2") (pin "68") (pinfunction "C4_68") (pintype "passive+no_connect"))
    )
    (net (code "86") (name "unconnected-(U2-C5-Pad69)") (class "Default")
      (node (ref "U2") (pin "69") (pinfunction "C5_69") (pintype "passive+no_connect"))
    )
    (net (code "87") (name "unconnected-(U2-C6-Pad110)") (class "Default")
      (node (ref "U2") (pin "110") (pinfunction "C6_110") (pintype "passive+no_connect"))
    )
    (net (code "88") (name "unconnected-(U2-C7-Pad111)") (class "Default")
      (node (ref "U2") (pin "111") (pinfunction "C7_111") (pintype "passive+no_connect"))
    )
    (net (code "89") (name "unconnected-(U2-C8-Pad112)") (class "Default")
      (node (ref "U2") (pin "112") (pinfunction "C8_112") (pintype "passive+no_connect"))
    )
    (net (code "90") (name "unconnected-(U2-C9-Pad7)") (class "Default")
      (node (ref "U2") (pin "7") (pinfunction "C9_7") (pintype "passive+no_connect"))
    )
    (net (code "91") (name "unconnected-(U2-C13-Pad44)") (class "Default")
      (node (ref "U2") (pin "44") (pinfunction "C13_44") (pintype "passive+no_connect"))
    )
    (net (code "92") (name "unconnected-(U2-D0-Pad15)") (class "Default")
      (node (ref "U2") (pin "15") (pinfunction "D0_15") (pintype "passive+no_connect"))
    )
    (net (code "93") (name "unconnected-(U2-D1-Pad16)") (class "Default")
      (node (ref "U2") (pin "16") (pinfunction "D1_16") (pintype "passive+no_connect"))
    )
    (net (code "94") (name "unconnected-(U2-D3-Pad18)") (class "Default")
      (node (ref "U2") (pin "18") (pinfunction "D3_18") (pintype "passive+no_connect"))
    )
    (net (code "95") (name "unconnected-(U2-D8-Pad95)") (class "Default")
      (node (ref "U2") (pin "95") (pinfunction "D8_95") (pintype "passive+no_connect"))
    )
    (net (code "96") (name "unconnected-(U2-D9-Pad96)") (class "Default")
      (node (ref "U2") (pin "96") (pinfunction "D9_96") (pintype "passive+no_connect"))
    )
    (net (code "97") (name "unconnected-(U2-D10-Pad97)") (class "Default")
      (node (ref "U2") (pin "97") (pinfunction "D10_97") (pintype "passive+no_connect"))
    )
    (net (code "98") (name "unconnected-(U2-D12-Pad99)") (class "Default")
      (node (ref "U2") (pin "99") (pinfunction "D12_99") (pintype "passive+no_connect"))
    )
    (net (code "99") (name "unconnected-(U2-D14-Pad101)") (class "Default")
      (node (ref "U2") (pin "101") (pinfunction "D14_101") (pintype "passive+no_connect"))
    )
    (net (code "100") (name "unconnected-(U2-D15-Pad102)") (class "Default")
      (node (ref "U2") (pin "102") (pinfunction "D15_102") (pintype "passive+no_connect"))
    )
    (net (code "101") (name "unconnected-(U2-E2-Pad39)") (class "Default")
      (node (ref "U2") (pin "39") (pinfunction "E2_39") (pintype "passive+no_connect"))
    )
    (net (code "102") (name "unconnected-(U2-E3-Pad40)") (class "Default")
      (node (ref "U2") (pin "40") (pinfunction "E3_40") (pintype "passive+no_connect"))
    )
    (net (code "103") (name "unconnected-(U2-E4-Pad41)") (class "Default")
      (node (ref "U2") (pin "41") (pinfunction "E4_41") (pintype "passive+no_connect"))
    )
    (net (code "104") (name "unconnected-(U2-E5-Pad42)") (class "Default")
      (node (ref "U2") (pin "42") (pinfunction "E5_42") (pintype "passive+no_connect"))
    )
    (net (code "105") (name "unconnected-(U2-E6-Pad43)") (class "Default")
      (node (ref "U2") (pin "43") (pinfunction "E6_43") (pintype "passive+no_connect"))
    )
    (net (code "106") (name "unconnected-(U2-E9-Pad82)") (class "Default")
      (node (ref "U2") (pin "82") (pinfunction "E9_82") (pintype "passive+no_connect"))
    )
    (net (code "107") (name "unconnected-(U2-E10-Pad83)") (class "Default")
      (node (ref "U2") (pin "83") (pinfunction "E10_83") (pintype "passive+no_connect"))
    )
    (net (code "108") (name "unconnected-(U2-E11-Pad84)") (class "Default")
      (node (ref "U2") (pin "84") (pinfunction "E11_84") (pintype "passive+no_connect"))
    )
    (net (code "109") (name "unconnected-(U2-E12-Pad85)") (class "Default")
      (node (ref "U2") (pin "85") (pinfunction "E12_85") (pintype "passive+no_connect"))
    )
    (net (code "110") (name "unconnected-(U2-E13-Pad86)") (class "Default")
      (node (ref "U2") (pin "86") (pinfunction "E13_86") (pintype "passive+no_connect"))
    )
    (net (code "111") (name "unconnected-(U2-E14-Pad87)") (class "Default")
      (node (ref "U2") (pin "87") (pinfunction "E14_87") (pintype "passive+no_connect"))
    )
    (net (code "112") (name "unconnected-(U2-E15-Pad88)") (class "Default")
      (node (ref "U2") (pin "88") (pinfunction "E15_88") (pintype "passive+no_connect"))
    )
    (net (code "113") (name "unconnected-(U2-F8-Pad53)") (class "Default")
      (node (ref "U2") (pin "53") (pinfunction "F8_53") (pintype "passive+no_connect"))
    )
    (net (code "114") (name "unconnected-(U2-F9-Pad54)") (class "Default")
      (node (ref "U2") (pin "54") (pinfunction "F9_54") (pintype "passive+no_connect"))
    )
    (net (code "115") (name "unconnected-(U2-F10-Pad55)") (class "Default")
      (node (ref "U2") (pin "55") (pinfunction "F10_55") (pintype "passive+no_connect"))
    )
    (net (code "116") (name "unconnected-(U2-F11-Pad73)") (class "Default")
      (node (ref "U2") (pin "73") (pinfunction "F11_73") (pintype "passive+no_connect"))
    )
    (net (code "117") (name "unconnected-(U2-F12-Pad74)") (class "Default")
      (node (ref "U2") (pin "74") (pinfunction "F12_74") (pintype "passive+no_connect"))
    )
    (net (code "118") (name "unconnected-(U2-F13-Pad75)") (class "Default")
      (node (ref "U2") (pin "75") (pinfunction "F13_75") (pintype "passive+no_connect"))
    )
    (net (code "119") (name "unconnected-(U2-F14-Pad76)") (class "Default")
      (node (ref "U2") (pin "76") (pinfunction "F14_76") (pintype "passive+no_connect"))
    )
    (net (code "120") (name "unconnected-(U2-F15-Pad77)") (class "Default")
      (node (ref "U2") (pin "77") (pinfunction "F15_77") (pintype "passive+no_connect"))
    )
    (net (code "121") (name "unconnected-(U2-G0-Pad78)") (class "Default")
      (node (ref "U2") (pin "78") (pinfunction "G0_78") (pintype "passive+no_connect"))
    )
    (net (code "122") (name "unconnected-(U2-G1-Pad79)") (class "Default")
      (node (ref "U2") (pin "79") (pinfunction "G1_79") (pintype "passive+no_connect"))
    )
    (net (code "123") (name "unconnected-(U2-G2-Pad103)") (class "Default")
      (node (ref "U2") (pin "103") (pinfunction "G2_103") (pintype "passive+no_connect"))
    )
    (net (code "124") (name "unconnected-(U2-G3-Pad104)") (class "Default")
      (node (ref "U2") (pin "104") (pinfunction "G3_104") (pintype "passive+no_connect"))
    )
    (net (code "125") (name "unconnected-(U2-G4-Pad105)") (class "Default")
      (node (ref "U2") (pin "105") (pinfunction "G4_105") (pintype "passive+no_connect"))
    )
    (net (code "126") (name "unconnected-(U2-G5-Pad106)") (class "Default")
      (node (ref "U2") (pin "106") (pinfunction "G5_106") (pintype "passive+no_connect"))
    )
    (net (code "127") (name "unconnected-(U2-G6-Pad107)") (class "Default")
      (node (ref "U2") (pin "107") (pinfunction "G6_107") (pintype "passive+no_connect"))
    )
    (net (code "128") (name "unconnected-(U2-G7-Pad108)") (class "Default")
      (node (ref "U2") (pin "108") (pinfunction "G7_108") (pintype "passive+no_connect"))
    )
    (net (code "129") (name "unconnected-(U2-G8-Pad109)") (class "Default")
      (node (ref "U2") (pin "109") (pinfunction "G8_109") (pintype "passive+no_connect"))
    )
    (net (code "130") (name "unconnected-(U2-G9-Pad24)") (class "Default")
      (node (ref "U2") (pin "24") (pinfunction "G9_24") (pintype "passive+no_connect"))
    )
    (net (code "131") (name "unconnected-(U2-G10-Pad23)") (class "Default")
      (node (ref "U2") (pin "23") (pinfunction "G10_23") (pintype "passive+no_connect"))
    )
    (net (code "132") (name "unconnected-(U2-G11-Pad26)") (class "Default")
      (node (ref "U2") (pin "26") (pinfunction "G11_26") (pintype "passive+no_connect"))
    )
    (net (code "133") (name "unconnected-(U2-G12-Pad25)") (class "Default")
      (node (ref "U2") (pin "25") (pinfunction "G12_25") (pintype "passive+no_connect"))
    )
    (net (code "134") (name "unconnected-(U2-G13-Pad28)") (class "Default")
      (node (ref "U2") (pin "28") (pinfunction "G13_28") (pintype "passive+no_connect"))
    )
    (net (code "135") (name "unconnected-(U2-G14-Pad27)") (class "Default")
      (node (ref "U2") (pin "27") (pinfunction "G14_27") (pintype "passive+no_connect"))
    )
    (net (code "136") (name "unconnected-(U2-G15-Pad30)") (class "Default")
      (node (ref "U2") (pin "30") (pinfunction "G15_30") (pintype "passive+no_connect"))
    )
    (net (code "137") (name "unconnected-(U3-2A0-Pad17)") (class "Default")
      (node (ref "U3") (pin "17") (pinfunction "2A0_17") (pintype "passive+no_connect"))
    )
    (net (code "138") (name "unconnected-(U3-2A1-Pad15)") (class "Default")
      (node (ref "U3") (pin "15") (pinfunction "2A1_15") (pintype "passive+no_connect"))
    )
    (net (code "139") (name "unconnected-(U3-2A2-Pad13)") (class "Default")
      (node (ref "U3") (pin "13") (pinfunction "2A2_13") (pintype "passive+no_connect"))
    )
    (net (code "140") (name "unconnected-(U3-2A3-Pad11)") (class "Default")
      (node (ref "U3") (pin "11") (pinfunction "2A3_11") (pintype "passive+no_connect"))
    )
    (net (code "141") (name "unconnected-(U3-2Y0-Pad3)") (class "Default")
      (node (ref "U3") (pin "3") (pinfunction "2Y0_3") (pintype "passive+no_connect"))
    )
    (net (code "142") (name "unconnected-(U3-2Y1-Pad5)") (class "Default")
      (node (ref "U3") (pin "5") (pinfunction "2Y1_5") (pintype "passive+no_connect"))
    )
    (net (code "143") (name "unconnected-(U3-2Y2-Pad7)") (class "Default")
      (node (ref "U3") (pin "7") (pinfunction "2Y2_7") (pintype "passive+no_connect"))
    )
    (net (code "144") (name "unconnected-(U3-2Y3-Pad9)") (class "Default")
      (node (ref "U3") (pin "9") (pinfunction "2Y3_9") (pintype "passive+no_connect"))
    )
    (net (code "145") (name "unconnected-(U4-NC-Pad4)") (class "Default")
      (node (ref "U4") (pin "4") (pinfunction "NC_4") (pintype "passive+no_connect"))
    )
    (net (code "146") (name "unconnected-(U5-NC-Pad4)") (class "Default")
      (node (ref "U5") (pin "4") (pinfunction "NC_4") (pintype "passive+no_connect"))
    )
    (net (code "147") (name "unconnected-(U6-NC-Pad4)") (class "Default")
      (node (ref "U6") (pin "4") (pinfunction "NC_4") (pintype "passive+no_connect"))
    )
  )
)
